# Son_BU_ESP32_V1.net
KiCad netlist of a schematic drawn in Altium Designer
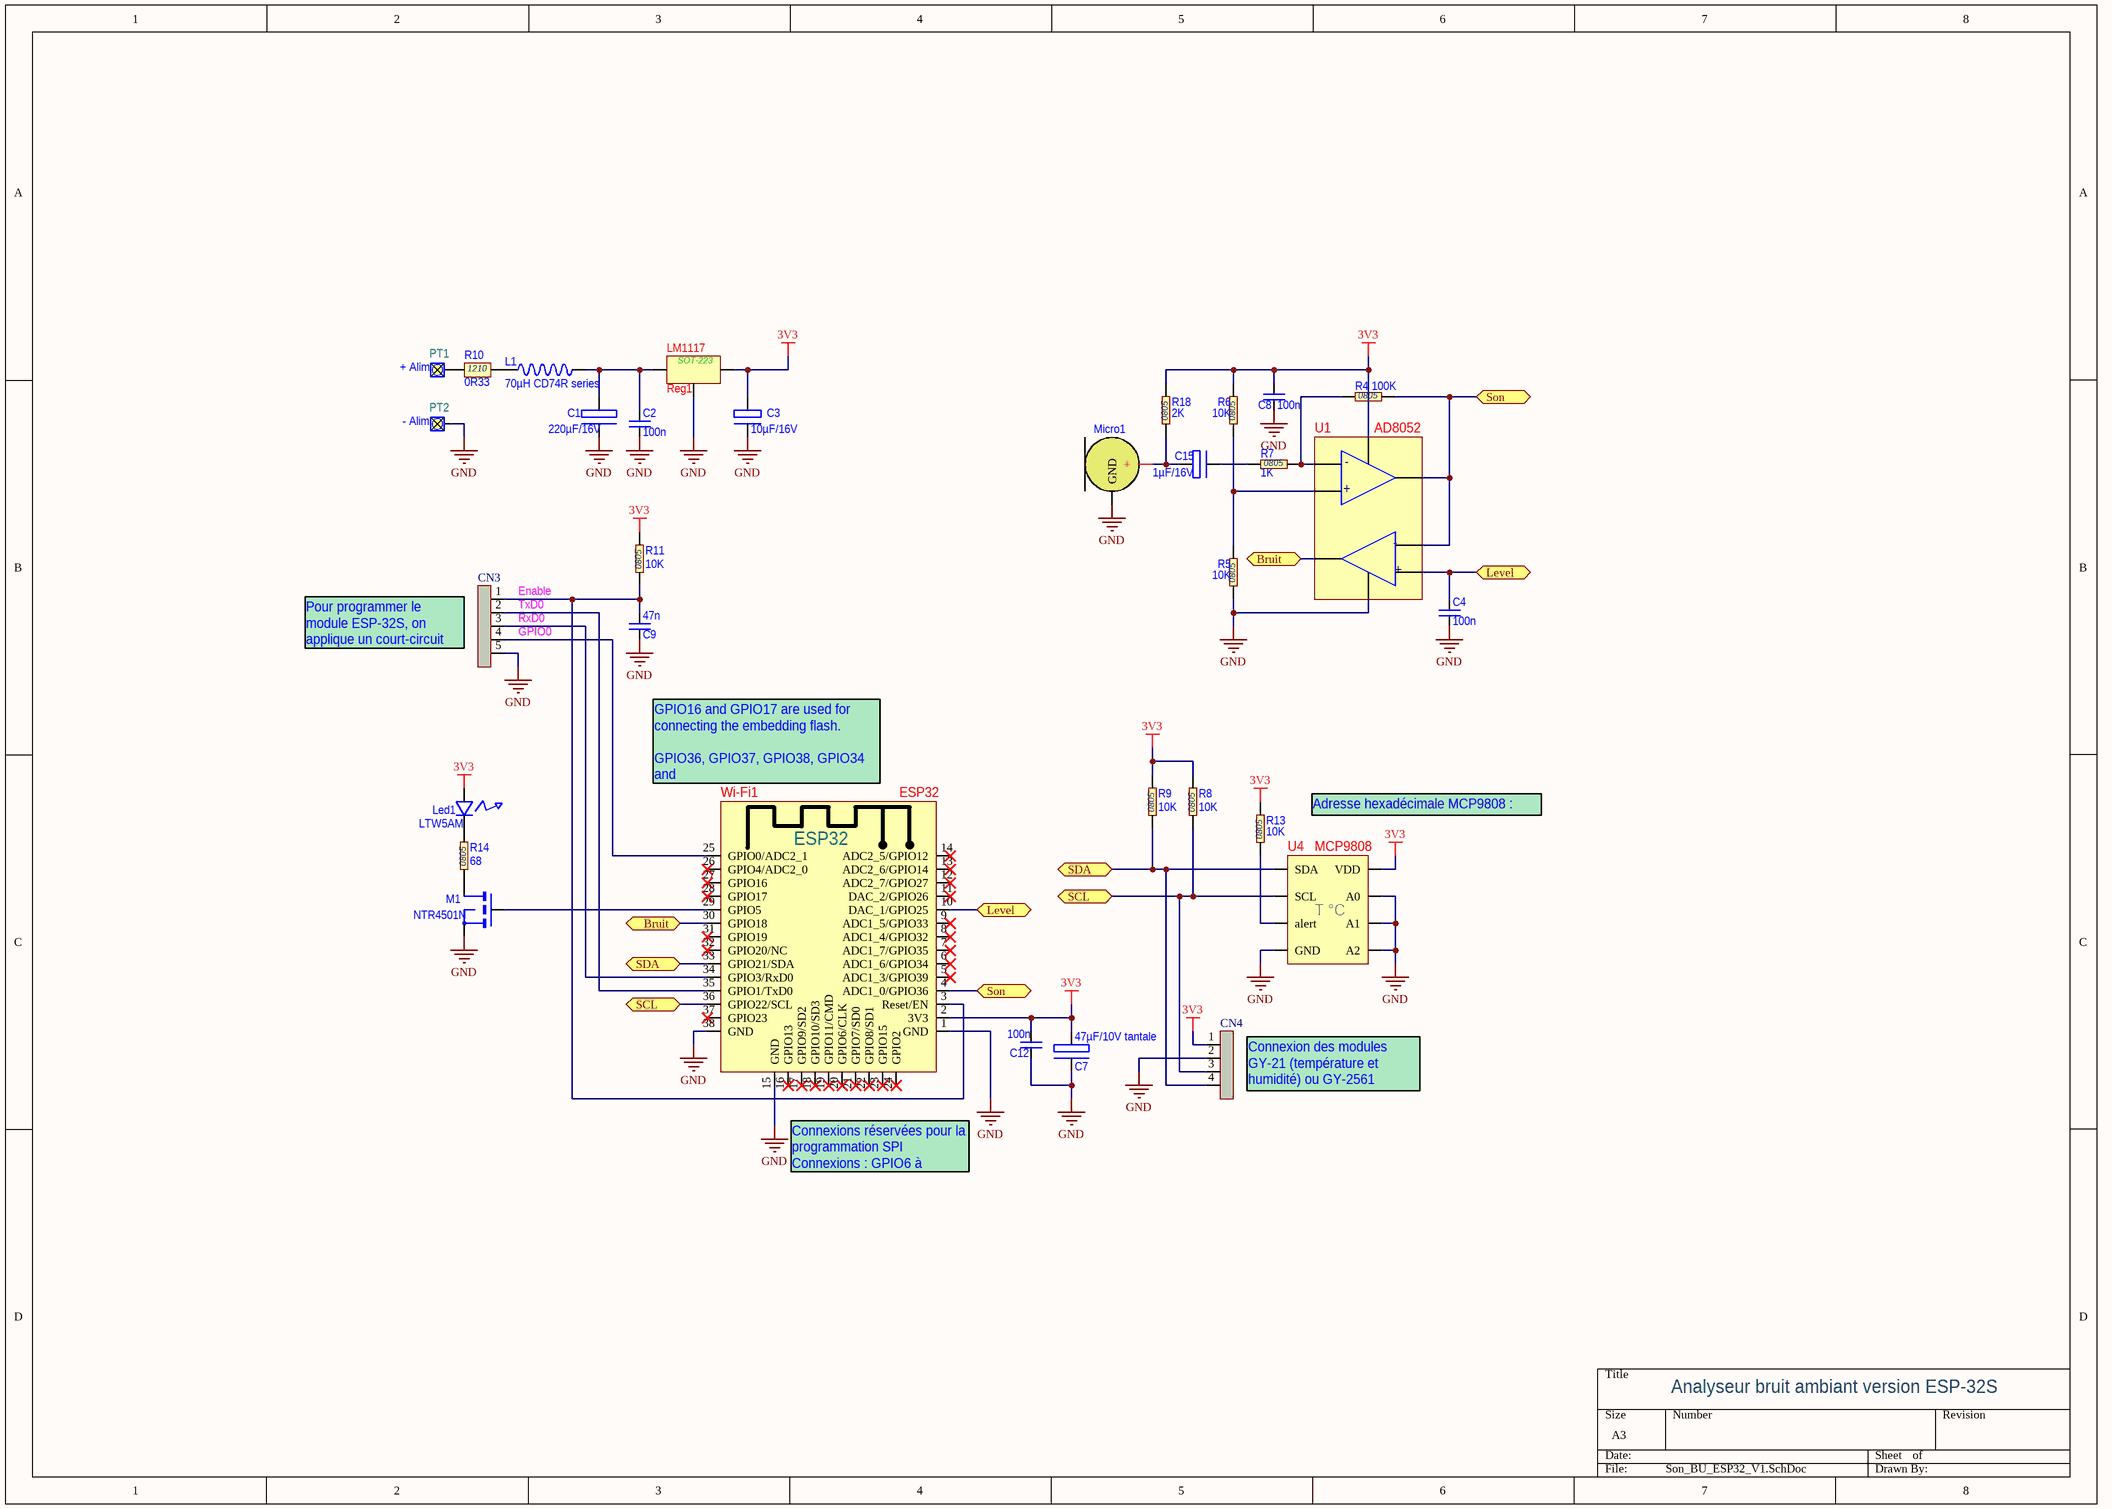
[diagram p0: Son_BU_ESP32_V1.SchDoc]

(export (version "E")
  (design (tool "Eeschema 10.0.6"))
  (components
    (comp (ref "C1")
      (value "220µF/16V")
      (footprint "7343-31")
      (description "253-5290 case 7343-31")
      (libsource (lib "CMS") (part "tantale 220µF/16V"))
    )
    (comp (ref "C2")
      (value "100n")
      (footprint "0805")
      (description "CMS 0805")
      (libsource (lib "CMS") (part "Cap_CMS_0805"))
    )
    (comp (ref "C3")
      (value "10µF/16V")
      (footprint "Tantale 10µF/16V")
      (description "145-7461 case 3216-18")
      (libsource (lib "CMS") (part "tantale 10µF/16V"))
    )
    (comp (ref "C4")
      (value "100n")
      (footprint "0805")
      (description "CMS 0805")
      (libsource (lib "CMS") (part "Cap_CMS_0805"))
    )
    (comp (ref "C7")
      (value "47µF/10V tantale")
      (footprint "tantale 47µF/10V")
      (description "175-4168")
      (libsource (lib "CMS") (part "tantale 47µF/10V"))
    )
    (comp (ref "C8")
      (value "100n")
      (footprint "0805")
      (description "CMS 0805")
      (libsource (lib "CMS") (part "Cap_CMS_0805"))
    )
    (comp (ref "C9")
      (value "47n")
      (footprint "0805")
      (description "CMS 0805")
      (libsource (lib "CMS") (part "Cap_CMS_0805"))
    )
    (comp (ref "C12")
      (value "100n")
      (footprint "0805")
      (description "CMS 0805")
      (libsource (lib "CMS") (part "Cap_CMS_0805"))
    )
    (comp (ref "C15")
      (value "1µF/16V")
      (footprint "3216-18")
      (description "145-7406 case 3216-18")
      (libsource (lib "CMS") (part "tantale 1µF/16V"))
    )
    (comp (ref "CN3")
      (value "inch_ligne 1x5")
      (footprint "INCH_1x5_droit")
      (description "Inch_1x5_droit")
      (libsource (lib "Connecteurs Contacts") (part "Inch_1x5_droit"))
    )
    (comp (ref "CN4")
      (value "inch_ligne 1x4")
      (footprint "INCH_1x4_droit")
      (description "Inch_1x4_droit")
      (libsource (lib "Connecteurs Contacts") (part "Inch_1x4_droit"))
    )
    (comp (ref "L1")
      (value "70µH CD74R series")
      (footprint "SELF CD74R")
      (description "SMT CD74R Aliexpress")
      (libsource (lib "CMS") (part "Self CD74R"))
    )
    (comp (ref "Led1")
      (value "LTW5AM")
      (footprint "LTW5AM")
      (description "LED Golden Dragon Plus")
      (libsource (lib "CMS") (part "LTW5AM LED"))
    )
    (comp (ref "M1")
      (value "NTR4501N")
      (footprint "SOT23 (NTR4501)")
      (description "MOSFET canal N")
      (libsource (lib "Transistors Bip Mos IGBT") (part "NTR4501N"))
    )
    (comp (ref "Micro1")
      (value "Electret")
      (footprint "Micro_electret simple")
      (description "Microphone électret")
      (libsource (lib "traversants") (part "Microphone_03"))
    )
    (comp (ref "PT1")
      (value "+ Alim")
      (footprint "Pointe de test")
      (description "pointe de test CI 133-6225")
      (libsource (lib "Connecteurs Contacts") (part "PTEST"))
    )
    (comp (ref "PT2")
      (value "- Alim")
      (footprint "Pointe de test")
      (description "pointe de test CI 133-6225")
      (libsource (lib "Connecteurs Contacts") (part "PTEST"))
    )
    (comp (ref "R4")
      (value "100K")
      (footprint "0805")
      (description "CMS 0805")
      (libsource (lib "") (part "Res CMS 0805_1"))
    )
    (comp (ref "R5")
      (value "10K")
      (footprint "0805")
      (description "CMS 0805")
      (libsource (lib "CMS") (part "Res CMS 0805"))
    )
    (comp (ref "R6")
      (value "10K")
      (footprint "0805")
      (description "CMS 0805")
      (libsource (lib "CMS") (part "Res CMS 0805"))
    )
    (comp (ref "R7")
      (value "1K")
      (footprint "0805")
      (description "CMS 0805")
      (libsource (lib "") (part "Res CMS 0805_1"))
    )
    (comp (ref "R8")
      (value "10K")
      (footprint "0805")
      (description "CMS 0805")
      (libsource (lib "CMS") (part "Res CMS 0805"))
    )
    (comp (ref "R9")
      (value "10K")
      (footprint "0805")
      (description "CMS 0805")
      (libsource (lib "CMS") (part "Res CMS 0805"))
    )
    (comp (ref "R10")
      (value "0R33")
      (footprint "1210")
      (description "CMS 1210")
      (libsource (lib "CMS") (part "Res CMS 1210 ERJ14B"))
    )
    (comp (ref "R11")
      (value "10K")
      (footprint "0805")
      (description "CMS 0805")
      (libsource (lib "CMS") (part "Res CMS 0805"))
    )
    (comp (ref "R13")
      (value "10K")
      (footprint "0805")
      (description "CMS 0805")
      (libsource (lib "CMS") (part "Res CMS 0805"))
    )
    (comp (ref "R14")
      (value "68")
      (footprint "0805")
      (description "CMS 0805")
      (libsource (lib "CMS") (part "Res CMS 0805"))
    )
    (comp (ref "R18")
      (value "2K")
      (footprint "0805")
      (description "CMS 0805")
      (libsource (lib "CMS") (part "Res CMS 0805"))
    )
    (comp (ref "Reg1")
      (value "LM1117")
      (footprint "SOT223")
      (description "Régulateur SOT-223")
      (libsource (lib "Convertisseurs_Régulateurs") (part "LM1117/800mA"))
    )
    (comp (ref "U1")
      (value "AD8052")
      (footprint "SOIC08")
      (description "AOP")
      (libsource (lib "CMS") (part "AD8052"))
    )
    (comp (ref "U4")
      (value "MCP9808")
      (footprint "MSOP-08")
      (description "Digital temperature Sensor")
      (libsource (lib "CMS") (part "MCP9808"))
    )
    (comp (ref "Wi-Fi1")
      (value "ESP32")
      (footprint "ESP32")
      (description "ESP32 module µC Bluetooth Wi-Fi")
      (libsource (lib "CMS") (part "ESP32"))
    )
  )
  (nets
    (net (code "1") (name "/Bruit") (class "Default")
      (node (ref "U1") (pin "7") (pinfunction "out_7") (pintype "passive"))
      (node (ref "Wi-Fi1") (pin "30") (pinfunction "GPIO18_30") (pintype "passive"))
    )
    (net (code "2") (name "/Enable") (class "Default")
      (node (ref "C9") (pin "2") (pinfunction "CT2_2") (pintype "passive"))
      (node (ref "CN3") (pin "1") (pintype "passive"))
      (node (ref "R11") (pin "1") (pinfunction "CT1_1") (pintype "passive"))
      (node (ref "Wi-Fi1") (pin "3") (pinfunction "Reset/EN_3") (pintype "passive"))
    )
    (net (code "3") (name "/GPIO0") (class "Default")
      (node (ref "CN3") (pin "4") (pintype "passive"))
      (node (ref "Wi-Fi1") (pin "25") (pinfunction "GPIO0/ADC2_1_25") (pintype "passive"))
    )
    (net (code "4") (name "/Level") (class "Default")
      (node (ref "C4") (pin "2") (pinfunction "CT2_2") (pintype "passive"))
      (node (ref "U1") (pin "5") (pinfunction "in+_5") (pintype "passive"))
      (node (ref "Wi-Fi1") (pin "10") (pinfunction "DAC_1/GPIO25_10") (pintype "passive"))
    )
    (net (code "5") (name "/RxD0") (class "Default")
      (node (ref "CN3") (pin "3") (pintype "passive"))
      (node (ref "Wi-Fi1") (pin "34") (pinfunction "GPIO3/RxD0_34") (pintype "passive"))
    )
    (net (code "6") (name "/SCL") (class "Default")
      (node (ref "CN4") (pin "3") (pintype "passive"))
      (node (ref "R8") (pin "1") (pinfunction "CT1_1") (pintype "passive"))
      (node (ref "U4") (pin "2") (pinfunction "SCL_2") (pintype "passive"))
      (node (ref "Wi-Fi1") (pin "36") (pinfunction "GPIO22/SCL_36") (pintype "passive"))
    )
    (net (code "7") (name "/SDA") (class "Default")
      (node (ref "CN4") (pin "4") (pintype "passive"))
      (node (ref "R9") (pin "1") (pinfunction "CT1_1") (pintype "passive"))
      (node (ref "U4") (pin "1") (pinfunction "SDA_1") (pintype "passive"))
      (node (ref "Wi-Fi1") (pin "33") (pinfunction "GPIO21/SDA_33") (pintype "passive"))
    )
    (net (code "8") (name "/Son") (class "Default")
      (node (ref "R4") (pin "2") (pinfunction "CT2_2") (pintype "passive"))
      (node (ref "U1") (pin "1") (pinfunction "out_1") (pintype "passive"))
      (node (ref "U1") (pin "6") (pinfunction "in-_6") (pintype "passive"))
      (node (ref "Wi-Fi1") (pin "4") (pinfunction "ADC1_0/GPIO36_4") (pintype "passive"))
    )
    (net (code "9") (name "/TxD0") (class "Default")
      (node (ref "CN3") (pin "2") (pintype "passive"))
      (node (ref "Wi-Fi1") (pin "35") (pinfunction "GPIO1/TxD0_35") (pintype "passive"))
    )
    (net (code "10") (name "3V3") (class "Default")
      (node (ref "C12") (pin "2") (pinfunction "CT2_2") (pintype "passive"))
      (node (ref "C3") (pin "1") (pinfunction "V+_1") (pintype "passive"))
      (node (ref "C7") (pin "1") (pinfunction "V+_1") (pintype "passive"))
      (node (ref "C8") (pin "2") (pinfunction "CT2_2") (pintype "passive"))
      (node (ref "CN4") (pin "1") (pintype "passive"))
      (node (ref "Led1") (pin "1") (pinfunction "anode_1") (pintype "passive"))
      (node (ref "R11") (pin "2") (pinfunction "CT2_2") (pintype "passive"))
      (node (ref "R13") (pin "2") (pinfunction "CT2_2") (pintype "passive"))
      (node (ref "R18") (pin "2") (pinfunction "CT2_2") (pintype "passive"))
      (node (ref "R6") (pin "2") (pinfunction "CT2_2") (pintype "passive"))
      (node (ref "R8") (pin "2") (pinfunction "CT2_2") (pintype "passive"))
      (node (ref "R9") (pin "2") (pinfunction "CT2_2") (pintype "passive"))
      (node (ref "Reg1") (pin "2") (pinfunction "OUT_2") (pintype "passive"))
      (node (ref "U1") (pin "8") (pinfunction "V+_8") (pintype "passive"))
      (node (ref "U4") (pin "8") (pinfunction "VDD_8") (pintype "passive"))
      (node (ref "Wi-Fi1") (pin "2") (pinfunction "3V3_2") (pintype "passive"))
    )
    (net (code "11") (name "GND") (class "Default")
      (node (ref "C1") (pin "2") (pinfunction "V-_2") (pintype "passive"))
      (node (ref "C12") (pin "1") (pinfunction "CT1_1") (pintype "passive"))
      (node (ref "C2") (pin "1") (pinfunction "CT1_1") (pintype "passive"))
      (node (ref "C3") (pin "2") (pinfunction "V-_2") (pintype "passive"))
      (node (ref "C4") (pin "1") (pinfunction "CT1_1") (pintype "passive"))
      (node (ref "C7") (pin "2") (pinfunction "V-_2") (pintype "passive"))
      (node (ref "C8") (pin "1") (pinfunction "CT1_1") (pintype "passive"))
      (node (ref "C9") (pin "1") (pinfunction "CT1_1") (pintype "passive"))
      (node (ref "CN3") (pin "5") (pintype "passive"))
      (node (ref "CN4") (pin "2") (pintype "passive"))
      (node (ref "M1") (pin "3") (pinfunction "S_3") (pintype "passive"))
      (node (ref "Micro1") (pin "0") (pinfunction "GND_0") (pintype "passive"))
      (node (ref "PT2") (pin "1") (pinfunction "PIN_1") (pintype "passive"))
      (node (ref "R5") (pin "1") (pinfunction "CT1_1") (pintype "passive"))
      (node (ref "Reg1") (pin "1") (pinfunction "GND_1") (pintype "passive"))
      (node (ref "U1") (pin "4") (pinfunction "V-_4") (pintype "passive"))
      (node (ref "U4") (pin "4") (pinfunction "GND_4") (pintype "passive"))
      (node (ref "U4") (pin "5") (pinfunction "A2_5") (pintype "passive"))
      (node (ref "U4") (pin "6") (pinfunction "A1_6") (pintype "passive"))
      (node (ref "U4") (pin "7") (pinfunction "A0_7") (pintype "passive"))
      (node (ref "Wi-Fi1") (pin "1") (pinfunction "GND_1") (pintype "passive"))
      (node (ref "Wi-Fi1") (pin "15") (pinfunction "GND_15") (pintype "passive"))
      (node (ref "Wi-Fi1") (pin "38") (pinfunction "GND_38") (pintype "passive"))
    )
    (net (code "12") (name "Net-(C1-V+)") (class "Default")
      (node (ref "C1") (pin "1") (pinfunction "V+_1") (pintype "passive"))
      (node (ref "C2") (pin "2") (pinfunction "CT2_2") (pintype "passive"))
      (node (ref "L1") (pin "1") (pinfunction "CT1_1") (pintype "passive"))
      (node (ref "Reg1") (pin "3") (pinfunction "IN_3") (pintype "passive"))
    )
    (net (code "13") (name "Net-(C15-V+)") (class "Default")
      (node (ref "C15") (pin "1") (pinfunction "V+_1") (pintype "passive"))
      (node (ref "Micro1") (pin "1") (pinfunction "+_1") (pintype "passive"))
      (node (ref "R18") (pin "1") (pinfunction "CT1_1") (pintype "passive"))
    )
    (net (code "14") (name "Net-(C15-V-)") (class "Default")
      (node (ref "C15") (pin "2") (pinfunction "V-_2") (pintype "passive"))
      (node (ref "R7") (pin "1") (pinfunction "CT1_1") (pintype "passive"))
    )
    (net (code "15") (name "Net-(L1-CT2)") (class "Default")
      (node (ref "L1") (pin "2") (pinfunction "CT2_2") (pintype "passive"))
      (node (ref "R10") (pin "2") (pinfunction "CT2_2") (pintype "passive"))
    )
    (net (code "16") (name "Net-(Led1-cathode)") (class "Default")
      (node (ref "Led1") (pin "2") (pinfunction "cathode_2") (pintype "passive"))
      (node (ref "R14") (pin "2") (pinfunction "CT2_2") (pintype "passive"))
    )
    (net (code "17") (name "Net-(M1-D)") (class "Default")
      (node (ref "M1") (pin "1") (pinfunction "D_1") (pintype "passive"))
      (node (ref "R14") (pin "1") (pinfunction "CT1_1") (pintype "passive"))
    )
    (net (code "18") (name "Net-(M1-G)") (class "Default")
      (node (ref "M1") (pin "2") (pinfunction "G_2") (pintype "passive"))
      (node (ref "Wi-Fi1") (pin "29") (pinfunction "GPIO5_29") (pintype "passive"))
    )
    (net (code "19") (name "Net-(PT1-PIN)") (class "Default")
      (node (ref "PT1") (pin "1") (pinfunction "PIN_1") (pintype "passive"))
      (node (ref "R10") (pin "1") (pinfunction "CT1_1") (pintype "passive"))
    )
    (net (code "20") (name "Net-(R4-CT1)") (class "Default")
      (node (ref "R4") (pin "1") (pinfunction "CT1_1") (pintype "passive"))
      (node (ref "R7") (pin "2") (pinfunction "CT2_2") (pintype "passive"))
      (node (ref "U1") (pin "2") (pinfunction "in-_2") (pintype "passive"))
    )
    (net (code "21") (name "Net-(R5-CT2)") (class "Default")
      (node (ref "R5") (pin "2") (pinfunction "CT2_2") (pintype "passive"))
      (node (ref "R6") (pin "1") (pinfunction "CT1_1") (pintype "passive"))
      (node (ref "U1") (pin "3") (pinfunction "in+_3") (pintype "passive"))
    )
    (net (code "22") (name "Net-(R13-CT1)") (class "Default")
      (node (ref "R13") (pin "1") (pinfunction "CT1_1") (pintype "passive"))
      (node (ref "U4") (pin "3") (pinfunction "alert_3") (pintype "passive"))
    )
    (net (code "23") (name "unconnected-(Wi-Fi1-ADC1_3{slash}GPIO39-Pad5)") (class "Default")
      (node (ref "Wi-Fi1") (pin "5") (pinfunction "ADC1_3/GPIO39_5") (pintype "passive+no_connect"))
    )
    (net (code "24") (name "unconnected-(Wi-Fi1-ADC1_4{slash}GPIO32-Pad8)") (class "Default")
      (node (ref "Wi-Fi1") (pin "8") (pinfunction "ADC1_4/GPIO32_8") (pintype "passive+no_connect"))
    )
    (net (code "25") (name "unconnected-(Wi-Fi1-ADC1_5{slash}GPIO33-Pad9)") (class "Default")
      (node (ref "Wi-Fi1") (pin "9") (pinfunction "ADC1_5/GPIO33_9") (pintype "passive+no_connect"))
    )
    (net (code "26") (name "unconnected-(Wi-Fi1-ADC1_6{slash}GPIO34-Pad6)") (class "Default")
      (node (ref "Wi-Fi1") (pin "6") (pinfunction "ADC1_6/GPIO34_6") (pintype "passive+no_connect"))
    )
    (net (code "27") (name "unconnected-(Wi-Fi1-ADC1_7{slash}GPIO35-Pad7)") (class "Default")
      (node (ref "Wi-Fi1") (pin "7") (pinfunction "ADC1_7/GPIO35_7") (pintype "passive+no_connect"))
    )
    (net (code "28") (name "unconnected-(Wi-Fi1-ADC2_5{slash}GPIO12-Pad14)") (class "Default")
      (node (ref "Wi-Fi1") (pin "14") (pinfunction "ADC2_5/GPIO12_14") (pintype "passive+no_connect"))
    )
    (net (code "29") (name "unconnected-(Wi-Fi1-ADC2_6{slash}GPIO14-Pad13)") (class "Default")
      (node (ref "Wi-Fi1") (pin "13") (pinfunction "ADC2_6/GPIO14_13") (pintype "passive+no_connect"))
    )
    (net (code "30") (name "unconnected-(Wi-Fi1-ADC2_7{slash}GPIO27-Pad12)") (class "Default")
      (node (ref "Wi-Fi1") (pin "12") (pinfunction "ADC2_7/GPIO27_12") (pintype "passive+no_connect"))
    )
    (net (code "31") (name "unconnected-(Wi-Fi1-DAC_2{slash}GPIO26-Pad11)") (class "Default")
      (node (ref "Wi-Fi1") (pin "11") (pinfunction "DAC_2/GPIO26_11") (pintype "passive+no_connect"))
    )
    (net (code "32") (name "unconnected-(Wi-Fi1-GPIO2-Pad24)") (class "Default")
      (node (ref "Wi-Fi1") (pin "24") (pinfunction "GPIO2_24") (pintype "passive+no_connect"))
    )
    (net (code "33") (name "unconnected-(Wi-Fi1-GPIO4{slash}ADC2_0-Pad26)") (class "Default")
      (node (ref "Wi-Fi1") (pin "26") (pinfunction "GPIO4/ADC2_0_26") (pintype "passive+no_connect"))
    )
    (net (code "34") (name "unconnected-(Wi-Fi1-GPIO6{slash}CLK-Pad20)") (class "Default")
      (node (ref "Wi-Fi1") (pin "20") (pinfunction "GPIO6/CLK_20") (pintype "passive+no_connect"))
    )
    (net (code "35") (name "unconnected-(Wi-Fi1-GPIO7{slash}SD0-Pad21)") (class "Default")
      (node (ref "Wi-Fi1") (pin "21") (pinfunction "GPIO7/SD0_21") (pintype "passive+no_connect"))
    )
    (net (code "36") (name "unconnected-(Wi-Fi1-GPIO8{slash}SD1-Pad22)") (class "Default")
      (node (ref "Wi-Fi1") (pin "22") (pinfunction "GPIO8/SD1_22") (pintype "passive+no_connect"))
    )
    (net (code "37") (name "unconnected-(Wi-Fi1-GPIO9{slash}SD2-Pad17)") (class "Default")
      (node (ref "Wi-Fi1") (pin "17") (pinfunction "GPIO9/SD2_17") (pintype "passive+no_connect"))
    )
    (net (code "38") (name "unconnected-(Wi-Fi1-GPIO10{slash}SD3-Pad18)") (class "Default")
      (node (ref "Wi-Fi1") (pin "18") (pinfunction "GPIO10/SD3_18") (pintype "passive+no_connect"))
    )
    (net (code "39") (name "unconnected-(Wi-Fi1-GPIO11{slash}CMD-Pad19)") (class "Default")
      (node (ref "Wi-Fi1") (pin "19") (pinfunction "GPIO11/CMD_19") (pintype "passive+no_connect"))
    )
    (net (code "40") (name "unconnected-(Wi-Fi1-GPIO13-Pad16)") (class "Default")
      (node (ref "Wi-Fi1") (pin "16") (pinfunction "GPIO13_16") (pintype "passive+no_connect"))
    )
    (net (code "41") (name "unconnected-(Wi-Fi1-GPIO15-Pad23)") (class "Default")
      (node (ref "Wi-Fi1") (pin "23") (pinfunction "GPIO15_23") (pintype "passive+no_connect"))
    )
    (net (code "42") (name "unconnected-(Wi-Fi1-GPIO16-Pad27)") (class "Default")
      (node (ref "Wi-Fi1") (pin "27") (pinfunction "GPIO16_27") (pintype "passive+no_connect"))
    )
    (net (code "43") (name "unconnected-(Wi-Fi1-GPIO17-Pad28)") (class "Default")
      (node (ref "Wi-Fi1") (pin "28") (pinfunction "GPIO17_28") (pintype "passive+no_connect"))
    )
    (net (code "44") (name "unconnected-(Wi-Fi1-GPIO19-Pad31)") (class "Default")
      (node (ref "Wi-Fi1") (pin "31") (pinfunction "GPIO19_31") (pintype "passive+no_connect"))
    )
    (net (code "45") (name "unconnected-(Wi-Fi1-GPIO20{slash}NC-Pad32)") (class "Default")
      (node (ref "Wi-Fi1") (pin "32") (pinfunction "GPIO20/NC_32") (pintype "passive+no_connect"))
    )
    (net (code "46") (name "unconnected-(Wi-Fi1-GPIO23-Pad37)") (class "Default")
      (node (ref "Wi-Fi1") (pin "37") (pinfunction "GPIO23_37") (pintype "passive+no_connect"))
    )
  )
)
